# interface.net
KiCad netlist of a schematic drawn in Altium Designer
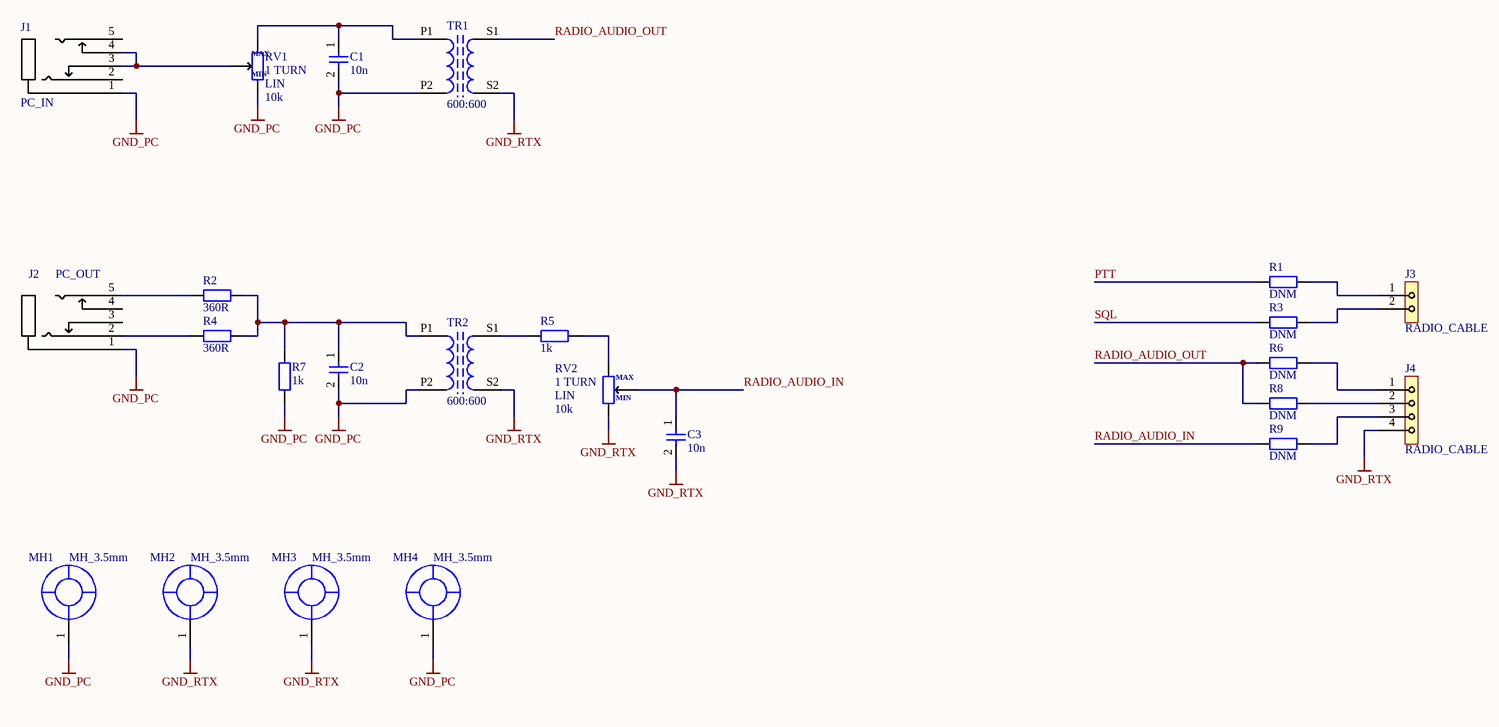
[diagram p0: interface.SchDoc]

(export (version "E")
  (design (tool "Eeschema 10.0.6"))
  (components
    (comp (ref "C1")
      (value "10n")
      (footprint "FP-1206-L_3_2_0_2-W_1_6_0-IPC_B")
      (libsource (lib "COMM_SHIELD_STUFF") (part "cap_unpol"))
    )
    (comp (ref "C2")
      (value "10n")
      (footprint "FP-1206-L_3_2_0_2-W_1_6_0-IPC_B")
      (libsource (lib "COMM_SHIELD_STUFF") (part "cap_unpol"))
    )
    (comp (ref "C3")
      (value "10n")
      (footprint "FP-1206-L_3_2_0_2-W_1_6_0-IPC_B")
      (libsource (lib "COMM_SHIELD_STUFF") (part "cap_unpol"))
    )
    (comp (ref "J1")
      (value "PC_IN")
      (footprint "ACA-115")
      (description "Jack, 3.5mm stereo, 2 switch")
      (libsource (lib "COMM_SHIELD_STUFF") (part "JACK_CONNECTOR"))
    )
    (comp (ref "J2")
      (value "PC_OUT")
      (footprint "ACA-115")
      (description "Jack, 3.5mm stereo, 2 switch")
      (libsource (lib "COMM_SHIELD_STUFF") (part "JACK_CONNECTOR"))
    )
    (comp (ref "J3")
      (value "RADIO_CABLE")
      (footprint "PIN_HEADER_1L_2P")
      (libsource (lib "COMM_SHIELD_STUFF") (part "PIN_HEADER_1L_2P"))
    )
    (comp (ref "J4")
      (value "RADIO_CABLE")
      (footprint "PIN_HEADER_1L_4P")
      (libsource (lib "COMM_SHIELD_STUFF") (part "PIN_HEADER_1L_4P"))
    )
    (comp (ref "MH1")
      (value "MH_3.5mm")
      (footprint "MOUNTING_HOLE_GROUNDED")
      (description "3.5mm grounded mounting hole")
      (libsource (lib "COMM_SHIELD_STUFF") (part "MOUNTING_HOLE_3.5mm_1"))
    )
    (comp (ref "MH2")
      (value "MH_3.5mm")
      (footprint "MOUNTING_HOLE_GROUNDED")
      (description "3.5mm grounded mounting hole")
      (libsource (lib "COMM_SHIELD_STUFF") (part "MOUNTING_HOLE_3.5mm_1"))
    )
    (comp (ref "MH3")
      (value "MH_3.5mm")
      (footprint "MOUNTING_HOLE_GROUNDED")
      (description "3.5mm grounded mounting hole")
      (libsource (lib "COMM_SHIELD_STUFF") (part "MOUNTING_HOLE_3.5mm_1"))
    )
    (comp (ref "MH4")
      (value "MH_3.5mm")
      (footprint "MOUNTING_HOLE_GROUNDED")
      (description "3.5mm grounded mounting hole")
      (libsource (lib "COMM_SHIELD_STUFF") (part "MOUNTING_HOLE_3.5mm_1"))
    )
    (comp (ref "R1")
      (value "Resistor")
      (footprint "FP-CRCW1206-e3-IPC_B")
      (description "EU symbol")
      (fields (field (name "RESISTANCE") "DNM"))
      (libsource (lib "COMM_SHIELD_STUFF") (part "Resistor"))
    )
    (comp (ref "R2")
      (value "Resistor")
      (footprint "FP-CRCW1206-e3-IPC_B")
      (description "EU symbol")
      (fields (field (name "RESISTANCE") "360R"))
      (libsource (lib "COMM_SHIELD_STUFF") (part "Resistor"))
    )
    (comp (ref "R3")
      (value "Resistor")
      (footprint "FP-CRCW1206-e3-IPC_B")
      (description "EU symbol")
      (fields (field (name "RESISTANCE") "DNM"))
      (libsource (lib "COMM_SHIELD_STUFF") (part "Resistor"))
    )
    (comp (ref "R4")
      (value "Resistor")
      (footprint "FP-CRCW1206-e3-IPC_B")
      (description "EU symbol")
      (fields (field (name "RESISTANCE") "360R"))
      (libsource (lib "COMM_SHIELD_STUFF") (part "Resistor"))
    )
    (comp (ref "R5")
      (value "Resistor")
      (footprint "FP-CRCW1206-e3-IPC_B")
      (description "EU symbol")
      (fields (field (name "RESISTANCE") "1k"))
      (libsource (lib "COMM_SHIELD_STUFF") (part "Resistor"))
    )
    (comp (ref "R6")
      (value "Resistor")
      (footprint "FP-CRCW1206-e3-IPC_B")
      (description "EU symbol")
      (fields (field (name "RESISTANCE") "DNM"))
      (libsource (lib "COMM_SHIELD_STUFF") (part "Resistor"))
    )
    (comp (ref "R7")
      (value "Resistor")
      (footprint "FP-CRCW1206-e3-IPC_B")
      (description "EU symbol")
      (fields (field (name "RESISTANCE") "1k"))
      (libsource (lib "COMM_SHIELD_STUFF") (part "Resistor"))
    )
    (comp (ref "R8")
      (value "Resistor")
      (footprint "FP-CRCW1206-e3-IPC_B")
      (description "EU symbol")
      (fields (field (name "RESISTANCE") "DNM"))
      (libsource (lib "COMM_SHIELD_STUFF") (part "Resistor"))
    )
    (comp (ref "R9")
      (value "Resistor")
      (footprint "FP-CRCW1206-e3-IPC_B")
      (description "EU symbol")
      (fields (field (name "RESISTANCE") "DNM"))
      (libsource (lib "COMM_SHIELD_STUFF") (part "Resistor"))
    )
    (comp (ref "RV1")
      (value "1 TURN")
      (footprint "POT_THT_200MIL")
      (fields (field (name "TYPE") "LIN") (field (name "RESISTANCE") "10k"))
      (libsource (lib "COMM_SHIELD_STUFF") (part "POT"))
    )
    (comp (ref "RV2")
      (value "1 TURN")
      (footprint "POT_THT_200MIL")
      (fields (field (name "TYPE") "LIN") (field (name "RESISTANCE") "10k"))
      (libsource (lib "COMM_SHIELD_STUFF") (part "POT"))
    )
    (comp (ref "TR1")
      (value "600:600")
      (footprint "TRANSFORMER_600_600_THT_RED")
      (description "1 Primer; 1 Seconder")
      (libsource (lib "COMM_SHIELD_STUFF") (part "Transformer"))
    )
    (comp (ref "TR2")
      (value "600:600")
      (footprint "TRANSFORMER_600_600_THT_RED")
      (description "1 Primer; 1 Seconder")
      (libsource (lib "COMM_SHIELD_STUFF") (part "Transformer"))
    )
  )
  (nets
    (net (code "1") (name "/PTT") (class "Default")
      (node (ref "R1") (pin "1") (pinfunction "1_1") (pintype "passive"))
    )
    (net (code "2") (name "/RADIO_AUDIO_IN") (class "Default")
      (node (ref "C3") (pin "1") (pinfunction "1_1") (pintype "passive"))
      (node (ref "R9") (pin "1") (pinfunction "1_1") (pintype "passive"))
      (node (ref "RV2") (pin "2") (pinfunction "2_2") (pintype "passive"))
    )
    (net (code "3") (name "/RADIO_AUDIO_OUT") (class "Default")
      (node (ref "R6") (pin "1") (pinfunction "1_1") (pintype "passive"))
      (node (ref "R8") (pin "1") (pinfunction "1_1") (pintype "passive"))
      (node (ref "TR1") (pin "S1") (pinfunction "S1_S1") (pintype "passive"))
    )
    (net (code "4") (name "/SQL") (class "Default")
      (node (ref "R3") (pin "1") (pinfunction "1_1") (pintype "passive"))
    )
    (net (code "5") (name "GND_PC") (class "Default")
      (node (ref "C1") (pin "2") (pinfunction "2_2") (pintype "passive"))
      (node (ref "C2") (pin "2") (pinfunction "2_2") (pintype "passive"))
      (node (ref "J1") (pin "1") (pinfunction "1_1") (pintype "passive"))
      (node (ref "J2") (pin "1") (pinfunction "1_1") (pintype "passive"))
      (node (ref "MH1") (pin "1") (pinfunction "1_1") (pintype "passive"))
      (node (ref "MH4") (pin "1") (pinfunction "1_1") (pintype "passive"))
      (node (ref "R7") (pin "2") (pinfunction "2_2") (pintype "passive"))
      (node (ref "RV1") (pin "1") (pinfunction "1_1") (pintype "passive"))
      (node (ref "TR1") (pin "P2") (pinfunction "P2_P2") (pintype "passive"))
      (node (ref "TR2") (pin "P2") (pinfunction "P2_P2") (pintype "passive"))
    )
    (net (code "6") (name "GND_RTX") (class "Default")
      (node (ref "C3") (pin "2") (pinfunction "2_2") (pintype "passive"))
      (node (ref "J4") (pin "4") (pinfunction "4_4") (pintype "passive"))
      (node (ref "MH2") (pin "1") (pinfunction "1_1") (pintype "passive"))
      (node (ref "MH3") (pin "1") (pinfunction "1_1") (pintype "passive"))
      (node (ref "RV2") (pin "1") (pinfunction "1_1") (pintype "passive"))
      (node (ref "TR1") (pin "S2") (pinfunction "S2_S2") (pintype "passive"))
      (node (ref "TR2") (pin "S2") (pinfunction "S2_S2") (pintype "passive"))
    )
    (net (code "7") (name "Net-(C1-Pad1)") (class "Default")
      (node (ref "C1") (pin "1") (pinfunction "1_1") (pintype "passive"))
      (node (ref "RV1") (pin "3") (pinfunction "3_3") (pintype "passive"))
      (node (ref "TR1") (pin "P1") (pinfunction "P1_P1") (pintype "passive"))
    )
    (net (code "8") (name "Net-(C2-Pad1)") (class "Default")
      (node (ref "C2") (pin "1") (pinfunction "1_1") (pintype "passive"))
      (node (ref "R2") (pin "2") (pinfunction "2_2") (pintype "passive"))
      (node (ref "R4") (pin "2") (pinfunction "2_2") (pintype "passive"))
      (node (ref "R7") (pin "1") (pinfunction "1_1") (pintype "passive"))
      (node (ref "TR2") (pin "P1") (pinfunction "P1_P1") (pintype "passive"))
    )
    (net (code "9") (name "Net-(J1-Pad3)") (class "Default")
      (node (ref "J1") (pin "3") (pinfunction "3_3") (pintype "passive"))
      (node (ref "J1") (pin "4") (pinfunction "4_4") (pintype "passive"))
      (node (ref "RV1") (pin "2") (pinfunction "2_2") (pintype "passive"))
    )
    (net (code "10") (name "Net-(J2-Pad2)") (class "Default")
      (node (ref "J2") (pin "2") (pinfunction "2_2") (pintype "passive"))
      (node (ref "R4") (pin "1") (pinfunction "1_1") (pintype "passive"))
    )
    (net (code "11") (name "Net-(J2-Pad5)") (class "Default")
      (node (ref "J2") (pin "5") (pinfunction "5_5") (pintype "passive"))
      (node (ref "R2") (pin "1") (pinfunction "1_1") (pintype "passive"))
    )
    (net (code "12") (name "Net-(J3-Pad1)") (class "Default")
      (node (ref "J3") (pin "1") (pinfunction "1_1") (pintype "passive"))
      (node (ref "R1") (pin "2") (pinfunction "2_2") (pintype "passive"))
    )
    (net (code "13") (name "Net-(J3-Pad2)") (class "Default")
      (node (ref "J3") (pin "2") (pinfunction "2_2") (pintype "passive"))
      (node (ref "R3") (pin "2") (pinfunction "2_2") (pintype "passive"))
    )
    (net (code "14") (name "Net-(J4-Pad1)") (class "Default")
      (node (ref "J4") (pin "1") (pinfunction "1_1") (pintype "passive"))
      (node (ref "R6") (pin "2") (pinfunction "2_2") (pintype "passive"))
    )
    (net (code "15") (name "Net-(J4-Pad2)") (class "Default")
      (node (ref "J4") (pin "2") (pinfunction "2_2") (pintype "passive"))
      (node (ref "R8") (pin "2") (pinfunction "2_2") (pintype "passive"))
    )
    (net (code "16") (name "Net-(J4-Pad3)") (class "Default")
      (node (ref "J4") (pin "3") (pinfunction "3_3") (pintype "passive"))
      (node (ref "R9") (pin "2") (pinfunction "2_2") (pintype "passive"))
    )
    (net (code "17") (name "Net-(R5-Pad1)") (class "Default")
      (node (ref "R5") (pin "1") (pinfunction "1_1") (pintype "passive"))
      (node (ref "TR2") (pin "S1") (pinfunction "S1_S1") (pintype "passive"))
    )
    (net (code "18") (name "Net-(R5-Pad2)") (class "Default")
      (node (ref "R5") (pin "2") (pinfunction "2_2") (pintype "passive"))
      (node (ref "RV2") (pin "3") (pinfunction "3_3") (pintype "passive"))
    )
    (net (code "19") (name "unconnected-(J1-Pad2)") (class "Default")
      (node (ref "J1") (pin "2") (pinfunction "2_2") (pintype "passive"))
    )
    (net (code "20") (name "unconnected-(J1-Pad5)") (class "Default")
      (node (ref "J1") (pin "5") (pinfunction "5_5") (pintype "passive"))
    )
    (net (code "21") (name "unconnected-(J2-Pad3)") (class "Default")
      (node (ref "J2") (pin "3") (pinfunction "3_3") (pintype "passive"))
    )
    (net (code "22") (name "unconnected-(J2-Pad4)") (class "Default")
      (node (ref "J2") (pin "4") (pinfunction "4_4") (pintype "passive"))
    )
  )
)
